# ButterflyFC.net
KiCad netlist of a schematic drawn in EAGLE
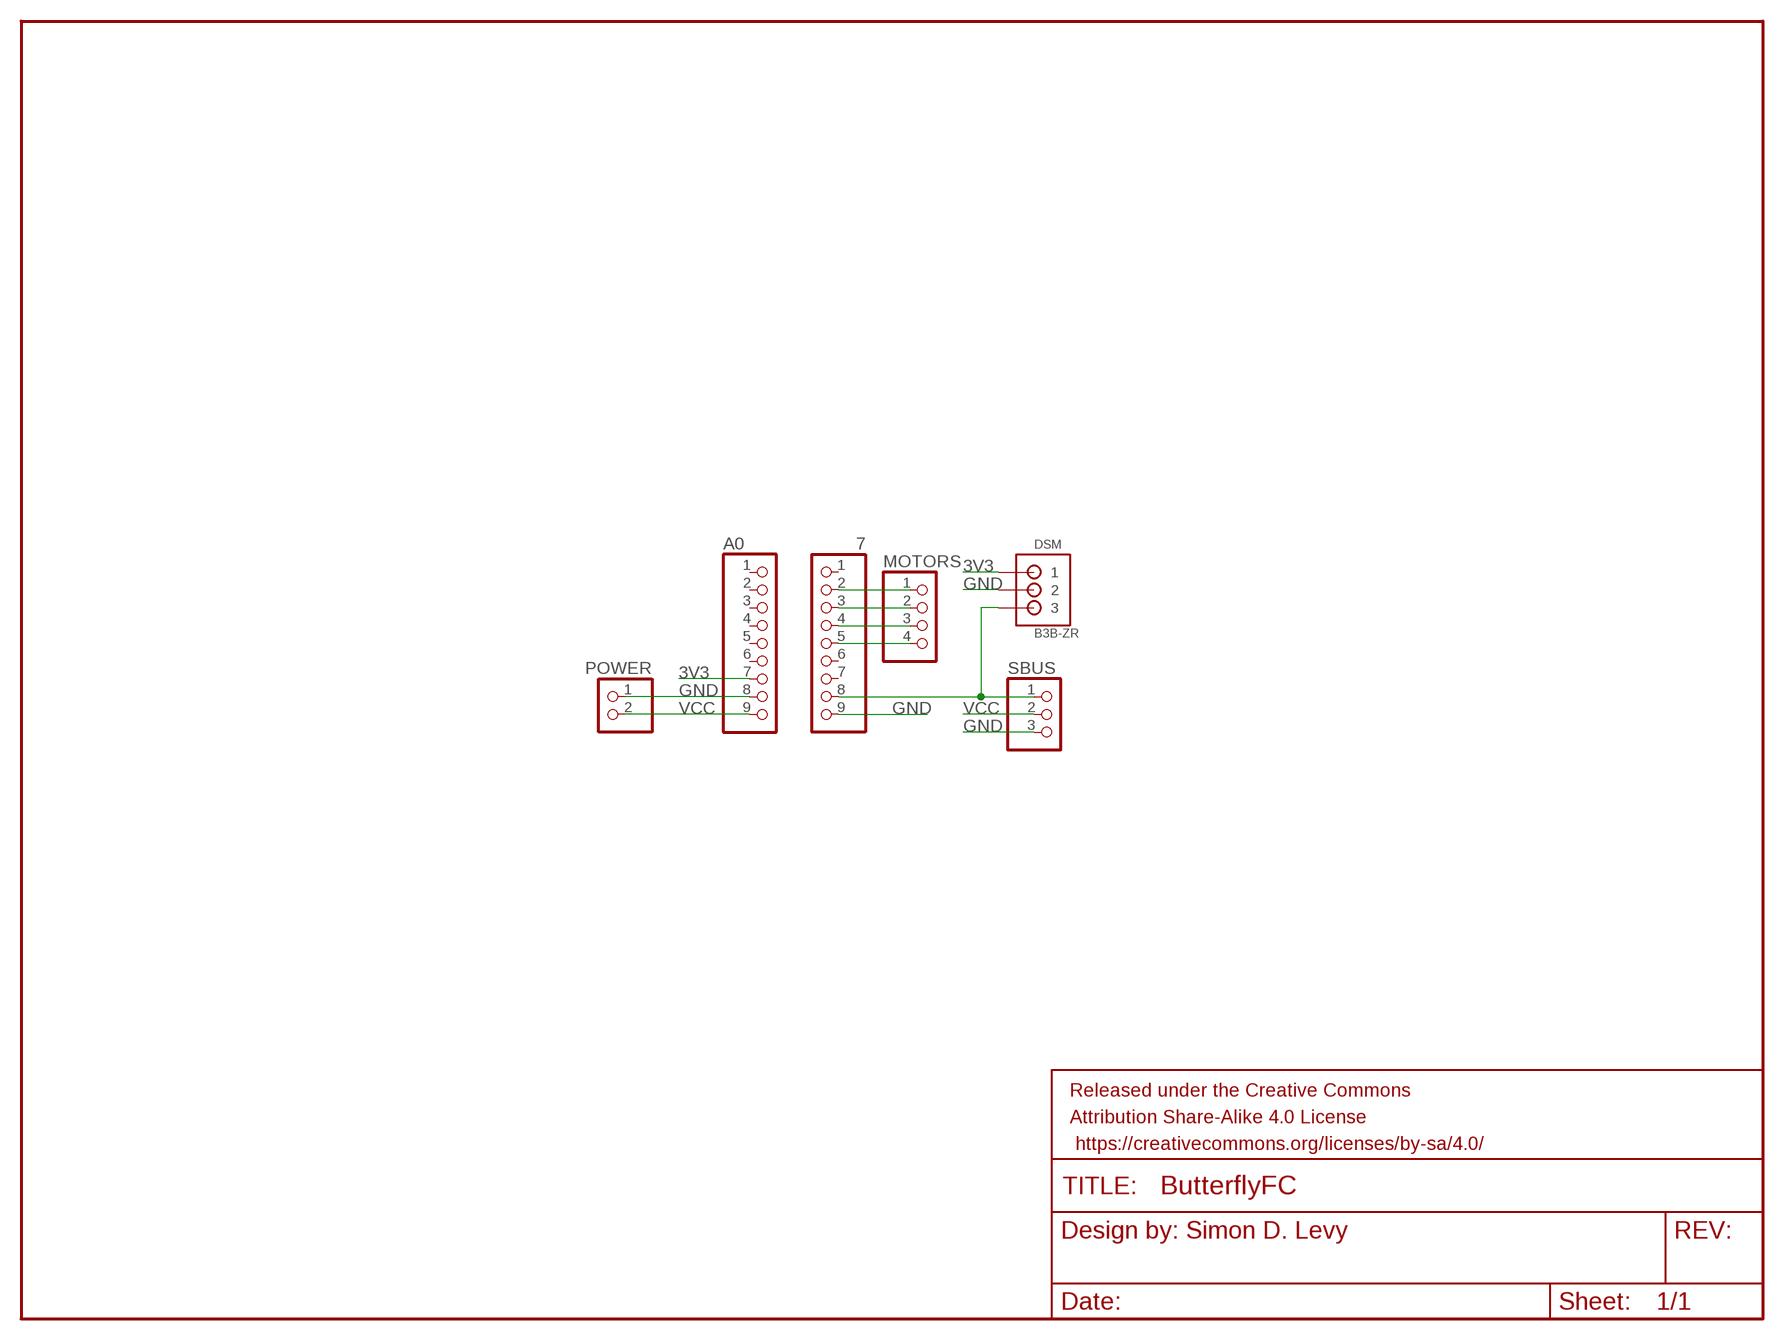
[diagram p0: schematic, sheet 1]

(export (version "E")
  (design (tool "Eeschema 10.0.6"))
  (components
    (comp (ref "7")
      (value "PINHD-1X9")
      (footprint "eagle-import:1X09")
      (libsource (lib "eagle-import") (part "PINHD-1X9"))
    )
    (comp (ref "A0")
      (value "PINHD-1X9")
      (footprint "eagle-import:1X09")
      (libsource (lib "eagle-import") (part "PINHD-1X9"))
    )
    (comp (ref "DSM")
      (value "B3B-ZR")
      (footprint "eagle-import:B3B-ZR")
      (libsource (lib "eagle-import") (part "B3B-ZR"))
    )
    (comp (ref "FRAME1")
      (value "FRAME-LETTER")
      (footprint "eagle-import:CREATIVE_COMMONS")
      (libsource (lib "eagle-import") (part "FRAME-LETTER"))
    )
    (comp (ref "MOTORS")
      (value "PINHD-1X4")
      (footprint "eagle-import:1X04")
      (libsource (lib "eagle-import") (part "PINHD-1X4"))
    )
    (comp (ref "POWER")
      (value "PINHD-1X2")
      (footprint "eagle-import:1X02")
      (libsource (lib "eagle-import") (part "PINHD-1X2"))
    )
    (comp (ref "SBUS")
      (value "PINHD-1X3")
      (footprint "eagle-import:1X03")
      (libsource (lib "eagle-import") (part "PINHD-1X3"))
    )
  )
  (nets
    (net (code "1") (name "/3V3") (class "Default")
      (node (ref "A0") (pin "7") (pinfunction "7_7") (pintype "passive"))
      (node (ref "DSM") (pin "1") (pinfunction "1_1") (pintype "bidirectional"))
    )
    (net (code "2") (name "/GND") (class "Default")
      (node (ref "7") (pin "9") (pinfunction "9_9") (pintype "passive"))
      (node (ref "A0") (pin "8") (pinfunction "8_8") (pintype "passive"))
      (node (ref "DSM") (pin "2") (pinfunction "2_2") (pintype "bidirectional"))
      (node (ref "POWER") (pin "1") (pinfunction "1_1") (pintype "passive"))
      (node (ref "SBUS") (pin "3") (pinfunction "3_3") (pintype "passive"))
    )
    (net (code "3") (name "/VCC") (class "Default")
      (node (ref "A0") (pin "9") (pinfunction "9_9") (pintype "passive"))
      (node (ref "POWER") (pin "2") (pinfunction "2_2") (pintype "passive"))
      (node (ref "SBUS") (pin "2") (pinfunction "2_2") (pintype "passive"))
    )
    (net (code "4") (name "Net-(7-Pad2)") (class "Default")
      (node (ref "7") (pin "2") (pinfunction "2_2") (pintype "passive"))
      (node (ref "MOTORS") (pin "1") (pinfunction "1_1") (pintype "passive"))
    )
    (net (code "5") (name "Net-(7-Pad3)") (class "Default")
      (node (ref "7") (pin "3") (pinfunction "3_3") (pintype "passive"))
      (node (ref "MOTORS") (pin "2") (pinfunction "2_2") (pintype "passive"))
    )
    (net (code "6") (name "Net-(7-Pad4)") (class "Default")
      (node (ref "7") (pin "4") (pinfunction "4_4") (pintype "passive"))
      (node (ref "MOTORS") (pin "3") (pinfunction "3_3") (pintype "passive"))
    )
    (net (code "7") (name "Net-(7-Pad5)") (class "Default")
      (node (ref "7") (pin "5") (pinfunction "5_5") (pintype "passive"))
      (node (ref "MOTORS") (pin "4") (pinfunction "4_4") (pintype "passive"))
    )
    (net (code "8") (name "Net-(7-Pad8)") (class "Default")
      (node (ref "7") (pin "8") (pinfunction "8_8") (pintype "passive"))
      (node (ref "DSM") (pin "3") (pinfunction "3_3") (pintype "bidirectional"))
      (node (ref "SBUS") (pin "1") (pinfunction "1_1") (pintype "passive"))
    )
    (net (code "9") (name "unconnected-(7-Pad1)") (class "Default")
      (node (ref "7") (pin "1") (pinfunction "1_1") (pintype "passive"))
    )
    (net (code "10") (name "unconnected-(7-Pad6)") (class "Default")
      (node (ref "7") (pin "6") (pinfunction "6_6") (pintype "passive"))
    )
    (net (code "11") (name "unconnected-(7-Pad7)") (class "Default")
      (node (ref "7") (pin "7") (pinfunction "7_7") (pintype "passive"))
    )
    (net (code "12") (name "unconnected-(A0-Pad1)") (class "Default")
      (node (ref "A0") (pin "1") (pinfunction "1_1") (pintype "passive"))
    )
    (net (code "13") (name "unconnected-(A0-Pad2)") (class "Default")
      (node (ref "A0") (pin "2") (pinfunction "2_2") (pintype "passive"))
    )
    (net (code "14") (name "unconnected-(A0-Pad3)") (class "Default")
      (node (ref "A0") (pin "3") (pinfunction "3_3") (pintype "passive"))
    )
    (net (code "15") (name "unconnected-(A0-Pad4)") (class "Default")
      (node (ref "A0") (pin "4") (pinfunction "4_4") (pintype "passive"))
    )
    (net (code "16") (name "unconnected-(A0-Pad5)") (class "Default")
      (node (ref "A0") (pin "5") (pinfunction "5_5") (pintype "passive"))
    )
    (net (code "17") (name "unconnected-(A0-Pad6)") (class "Default")
      (node (ref "A0") (pin "6") (pinfunction "6_6") (pintype "passive"))
    )
  )
)
